# Balancer_4S.net
KiCad netlist of a schematic drawn in EAGLE
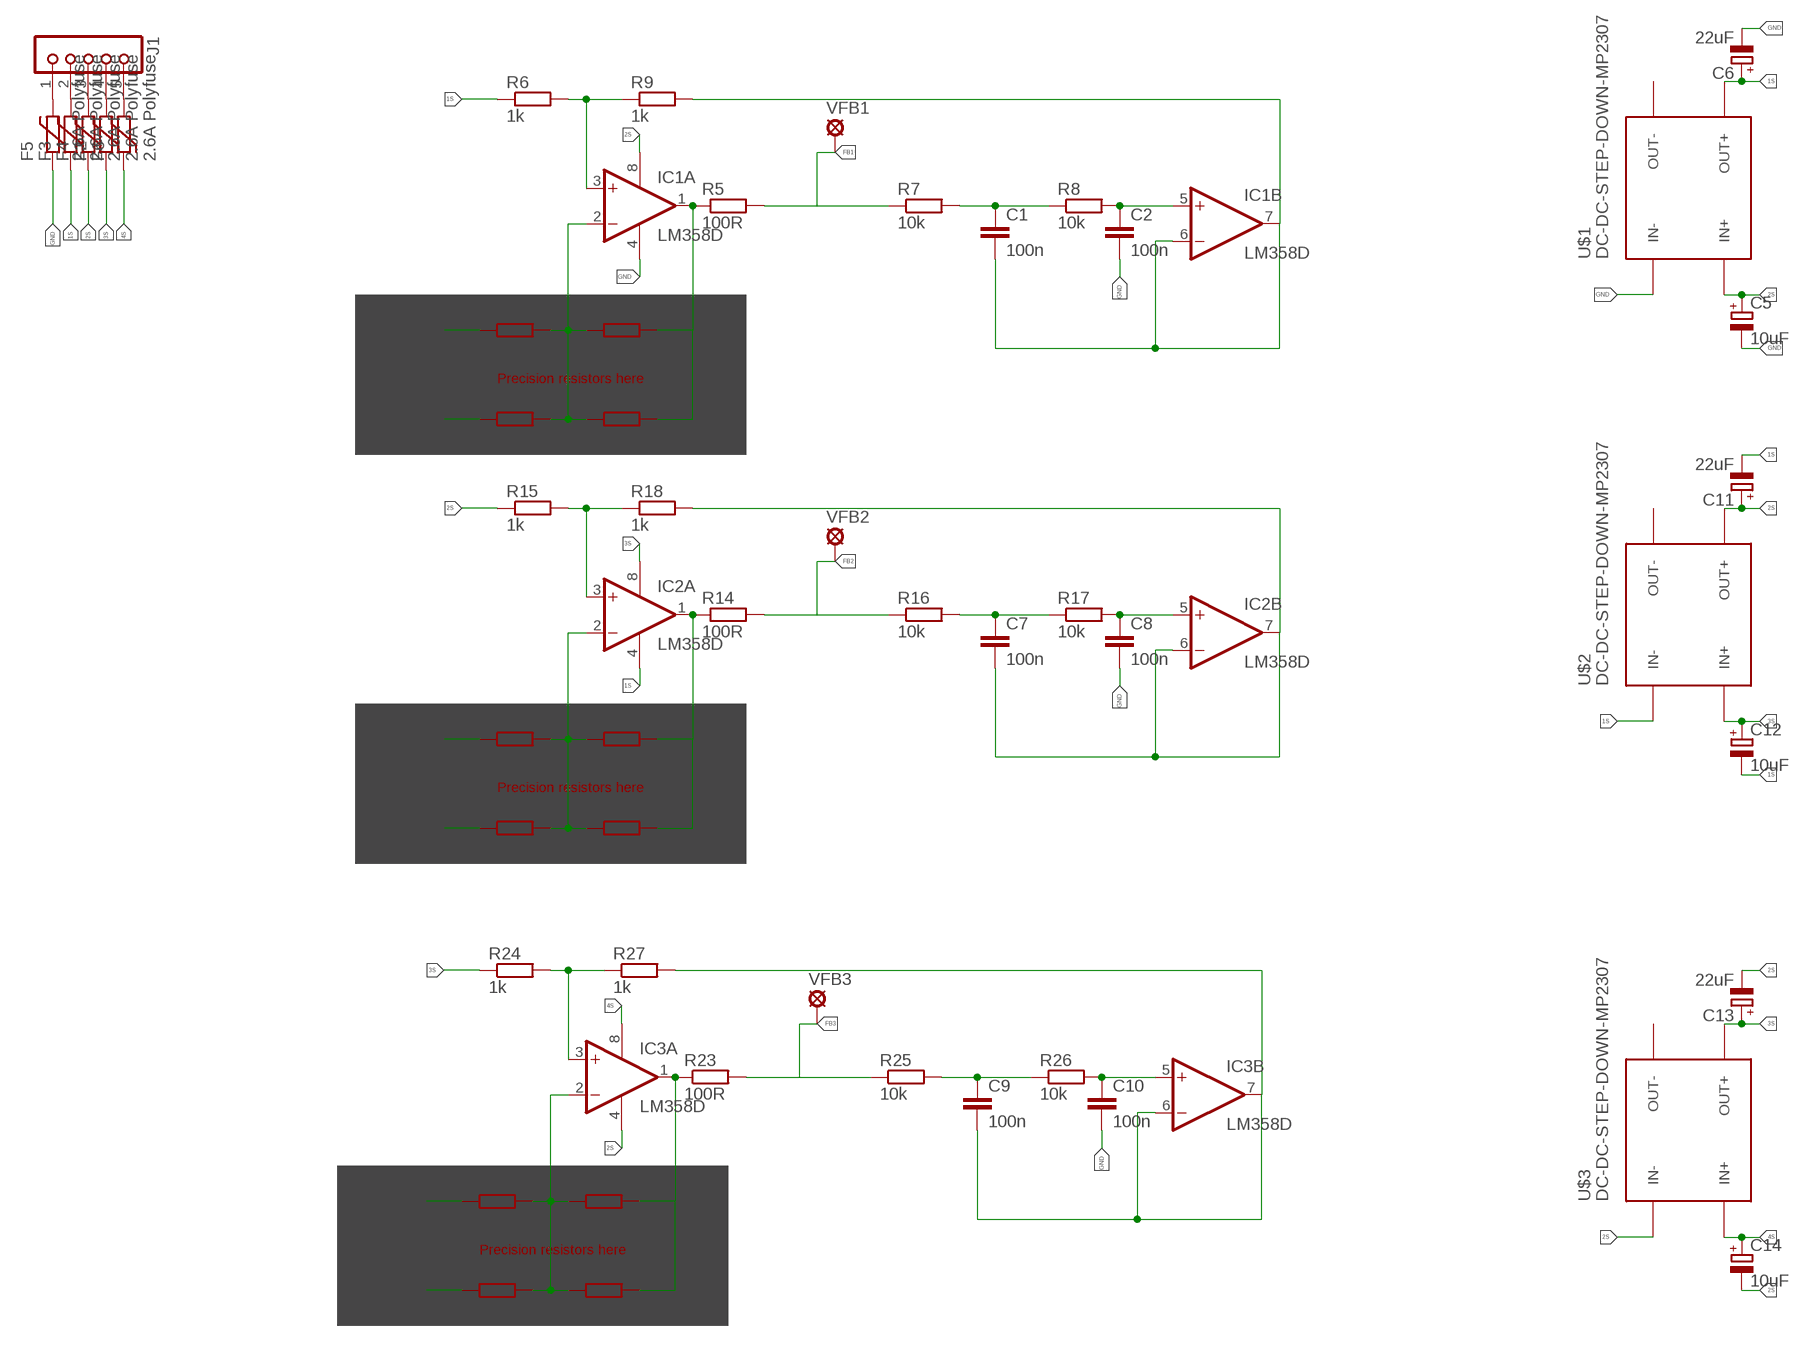
[diagram p0: schematic, sheet 1]

(export (version "E")
  (design (tool "Eeschema 10.0.6"))
  (components
    (comp (ref "C1")
      (value "100n")
      (footprint "eagle-import:C0805K")
      (libsource (lib "eagle-import") (part "C-EUC0805K"))
    )
    (comp (ref "C2")
      (value "100n")
      (footprint "eagle-import:C0805K")
      (libsource (lib "eagle-import") (part "C-EUC0805K"))
    )
    (comp (ref "C5")
      (value "10uF")
      (footprint "eagle-import:E2,5-6E")
      (libsource (lib "eagle-import") (part "CPOL-EUE2,5-6E"))
    )
    (comp (ref "C6")
      (value "22uF")
      (footprint "eagle-import:E2,5-6E")
      (libsource (lib "eagle-import") (part "CPOL-EUE2,5-6E"))
    )
    (comp (ref "C7")
      (value "100n")
      (footprint "eagle-import:C0805K")
      (libsource (lib "eagle-import") (part "C-EUC0805K"))
    )
    (comp (ref "C8")
      (value "100n")
      (footprint "eagle-import:C0805K")
      (libsource (lib "eagle-import") (part "C-EUC0805K"))
    )
    (comp (ref "C9")
      (value "100n")
      (footprint "eagle-import:C0805K")
      (libsource (lib "eagle-import") (part "C-EUC0805K"))
    )
    (comp (ref "C10")
      (value "100n")
      (footprint "eagle-import:C0805K")
      (libsource (lib "eagle-import") (part "C-EUC0805K"))
    )
    (comp (ref "C11")
      (value "22uF")
      (footprint "eagle-import:E2,5-6E")
      (libsource (lib "eagle-import") (part "CPOL-EUE2,5-6E"))
    )
    (comp (ref "C12")
      (value "10uF")
      (footprint "eagle-import:E2,5-6E")
      (libsource (lib "eagle-import") (part "CPOL-EUE2,5-6E"))
    )
    (comp (ref "C13")
      (value "22uF")
      (footprint "eagle-import:E2,5-6E")
      (libsource (lib "eagle-import") (part "CPOL-EUE2,5-6E"))
    )
    (comp (ref "C14")
      (value "10uF")
      (footprint "eagle-import:E2,5-6E")
      (libsource (lib "eagle-import") (part "CPOL-EUE2,5-6E"))
    )
    (comp (ref "F2")
      (value "2.6A Polyfuse")
      (footprint "eagle-import:1812L")
      (libsource (lib "eagle-import") (part "1812L"))
    )
    (comp (ref "F3")
      (value "2.6A Polyfuse")
      (footprint "eagle-import:1812L")
      (libsource (lib "eagle-import") (part "1812L"))
    )
    (comp (ref "F4")
      (value "2.6A Polyfuse")
      (footprint "eagle-import:1812L")
      (libsource (lib "eagle-import") (part "1812L"))
    )
    (comp (ref "F5")
      (value "2.6A Polyfuse")
      (footprint "eagle-import:1812L")
      (libsource (lib "eagle-import") (part "1812L"))
    )
    (comp (ref "F6")
      (value "2.6A Polyfuse")
      (footprint "eagle-import:1812L")
      (libsource (lib "eagle-import") (part "1812L"))
    )
    (comp (ref "IC1")
      (value "LM358D")
      (footprint "eagle-import:SO08")
      (libsource (lib "eagle-import") (part "LM358D"))
    )
    (comp (ref "IC2")
      (value "LM358D")
      (footprint "eagle-import:SO08")
      (libsource (lib "eagle-import") (part "LM358D"))
    )
    (comp (ref "IC3")
      (value "LM358D")
      (footprint "eagle-import:SO08")
      (libsource (lib "eagle-import") (part "LM358D"))
    )
    (comp (ref "J1")
      (value "JU05")
      (footprint "eagle-import:JU05")
      (libsource (lib "eagle-import") (part "JU05"))
    )
    (comp (ref "R1")
      (value "1k")
      (footprint "eagle-import:0204_7")
      (libsource (lib "eagle-import") (part "resistor_R-EU_0204/7"))
    )
    (comp (ref "R2")
      (value "1k")
      (footprint "eagle-import:0204_7")
      (libsource (lib "eagle-import") (part "resistor_R-EU_0204/7"))
    )
    (comp (ref "R3")
      (value "1k")
      (footprint "eagle-import:0204_7")
      (libsource (lib "eagle-import") (part "resistor_R-EU_0204/7"))
    )
    (comp (ref "R4")
      (value "1k")
      (footprint "eagle-import:0204_7")
      (libsource (lib "eagle-import") (part "resistor_R-EU_0204/7"))
    )
    (comp (ref "R5")
      (value "100R")
      (footprint "eagle-import:M0805")
      (libsource (lib "eagle-import") (part "R-EU_M0805"))
    )
    (comp (ref "R6")
      (value "1k")
      (footprint "eagle-import:M0805")
      (libsource (lib "eagle-import") (part "R-EU_M0805"))
    )
    (comp (ref "R7")
      (value "10k")
      (footprint "eagle-import:M0805")
      (libsource (lib "eagle-import") (part "R-EU_M0805"))
    )
    (comp (ref "R8")
      (value "10k")
      (footprint "eagle-import:M0805")
      (libsource (lib "eagle-import") (part "R-EU_M0805"))
    )
    (comp (ref "R9")
      (value "1k")
      (footprint "eagle-import:M0805")
      (libsource (lib "eagle-import") (part "R-EU_M0805"))
    )
    (comp (ref "R10")
      (value "1k")
      (footprint "eagle-import:0204_7")
      (libsource (lib "eagle-import") (part "resistor_R-EU_0204/7"))
    )
    (comp (ref "R11")
      (value "1k")
      (footprint "eagle-import:0204_7")
      (libsource (lib "eagle-import") (part "resistor_R-EU_0204/7"))
    )
    (comp (ref "R12")
      (value "1k")
      (footprint "eagle-import:0204_7")
      (libsource (lib "eagle-import") (part "resistor_R-EU_0204/7"))
    )
    (comp (ref "R13")
      (value "1k")
      (footprint "eagle-import:0204_7")
      (libsource (lib "eagle-import") (part "resistor_R-EU_0204/7"))
    )
    (comp (ref "R14")
      (value "100R")
      (footprint "eagle-import:M0805")
      (libsource (lib "eagle-import") (part "R-EU_M0805"))
    )
    (comp (ref "R15")
      (value "1k")
      (footprint "eagle-import:M0805")
      (libsource (lib "eagle-import") (part "R-EU_M0805"))
    )
    (comp (ref "R16")
      (value "10k")
      (footprint "eagle-import:M0805")
      (libsource (lib "eagle-import") (part "R-EU_M0805"))
    )
    (comp (ref "R17")
      (value "10k")
      (footprint "eagle-import:M0805")
      (libsource (lib "eagle-import") (part "R-EU_M0805"))
    )
    (comp (ref "R18")
      (value "1k")
      (footprint "eagle-import:M0805")
      (libsource (lib "eagle-import") (part "R-EU_M0805"))
    )
    (comp (ref "R19")
      (value "1k")
      (footprint "eagle-import:0204_7")
      (libsource (lib "eagle-import") (part "resistor_R-EU_0204/7"))
    )
    (comp (ref "R20")
      (value "1k")
      (footprint "eagle-import:0204_7")
      (libsource (lib "eagle-import") (part "resistor_R-EU_0204/7"))
    )
    (comp (ref "R21")
      (value "1k")
      (footprint "eagle-import:0204_7")
      (libsource (lib "eagle-import") (part "resistor_R-EU_0204/7"))
    )
    (comp (ref "R22")
      (value "1k")
      (footprint "eagle-import:0204_7")
      (libsource (lib "eagle-import") (part "resistor_R-EU_0204/7"))
    )
    (comp (ref "R23")
      (value "100R")
      (footprint "eagle-import:M0805")
      (libsource (lib "eagle-import") (part "R-EU_M0805"))
    )
    (comp (ref "R24")
      (value "1k")
      (footprint "eagle-import:M0805")
      (libsource (lib "eagle-import") (part "R-EU_M0805"))
    )
    (comp (ref "R25")
      (value "10k")
      (footprint "eagle-import:M0805")
      (libsource (lib "eagle-import") (part "R-EU_M0805"))
    )
    (comp (ref "R26")
      (value "10k")
      (footprint "eagle-import:M0805")
      (libsource (lib "eagle-import") (part "R-EU_M0805"))
    )
    (comp (ref "R27")
      (value "1k")
      (footprint "eagle-import:M0805")
      (libsource (lib "eagle-import") (part "R-EU_M0805"))
    )
    (comp (ref "U$1")
      (value "DC-DC-STEP-DOWN-MP2307")
      (footprint "eagle-import:DC-DC-STEP-DOWN-MP2307")
      (libsource (lib "eagle-import") (part "DC-DC-STEP-DOWN-MP2307"))
    )
    (comp (ref "U$2")
      (value "DC-DC-STEP-DOWN-MP2307")
      (footprint "eagle-import:DC-DC-STEP-DOWN-MP2307")
      (libsource (lib "eagle-import") (part "DC-DC-STEP-DOWN-MP2307"))
    )
    (comp (ref "U$3")
      (value "DC-DC-STEP-DOWN-MP2307")
      (footprint "eagle-import:DC-DC-STEP-DOWN-MP2307")
      (libsource (lib "eagle-import") (part "DC-DC-STEP-DOWN-MP2307"))
    )
    (comp (ref "VFB1")
      (value "MCS08")
      (footprint "eagle-import:MCS08")
      (libsource (lib "eagle-import") (part "MCS08"))
    )
    (comp (ref "VFB2")
      (value "MCS08")
      (footprint "eagle-import:MCS08")
      (libsource (lib "eagle-import") (part "MCS08"))
    )
    (comp (ref "VFB3")
      (value "MCS08")
      (footprint "eagle-import:MCS08")
      (libsource (lib "eagle-import") (part "MCS08"))
    )
  )
  (nets
    (net (code "1") (name "1S") (class "Default")
      (node (ref "C11") (pin "-") (pinfunction "-_-") (pintype "passive"))
      (node (ref "C12") (pin "-") (pinfunction "-_-") (pintype "passive"))
      (node (ref "C6") (pin "+") (pinfunction "+_+") (pintype "passive"))
      (node (ref "F3") (pin "P$1") (pinfunction "1_P$1") (pintype "passive"))
      (node (ref "IC2") (pin "4") (pinfunction "V-_4") (pintype "power_in"))
      (node (ref "R12") (pin "1") (pinfunction "1_1") (pintype "passive"))
      (node (ref "R6") (pin "1") (pinfunction "1_1") (pintype "passive"))
      (node (ref "U$1") (pin "OUT+") (pinfunction "OUT+_OUT+") (pintype "bidirectional"))
      (node (ref "U$2") (pin "IN-") (pinfunction "IN-_IN-") (pintype "bidirectional"))
    )
    (net (code "2") (name "2S") (class "Default")
      (node (ref "C11") (pin "+") (pinfunction "+_+") (pintype "passive"))
      (node (ref "C13") (pin "-") (pinfunction "-_-") (pintype "passive"))
      (node (ref "C14") (pin "-") (pinfunction "-_-") (pintype "passive"))
      (node (ref "C5") (pin "+") (pinfunction "+_+") (pintype "passive"))
      (node (ref "F4") (pin "P$1") (pinfunction "1_P$1") (pintype "passive"))
      (node (ref "IC1") (pin "8") (pinfunction "V+_8") (pintype "power_in"))
      (node (ref "IC3") (pin "4") (pinfunction "V-_4") (pintype "power_in"))
      (node (ref "R1") (pin "1") (pinfunction "1_1") (pintype "passive"))
      (node (ref "R15") (pin "1") (pinfunction "1_1") (pintype "passive"))
      (node (ref "R21") (pin "1") (pinfunction "1_1") (pintype "passive"))
      (node (ref "U$1") (pin "IN+") (pinfunction "IN+_IN+") (pintype "bidirectional"))
      (node (ref "U$2") (pin "OUT+") (pinfunction "OUT+_OUT+") (pintype "bidirectional"))
      (node (ref "U$3") (pin "IN-") (pinfunction "IN-_IN-") (pintype "bidirectional"))
    )
    (net (code "3") (name "3S") (class "Default")
      (node (ref "C12") (pin "+") (pinfunction "+_+") (pintype "passive"))
      (node (ref "C13") (pin "+") (pinfunction "+_+") (pintype "passive"))
      (node (ref "F2") (pin "P$1") (pinfunction "1_P$1") (pintype "passive"))
      (node (ref "IC2") (pin "8") (pinfunction "V+_8") (pintype "power_in"))
      (node (ref "R10") (pin "1") (pinfunction "1_1") (pintype "passive"))
      (node (ref "R24") (pin "1") (pinfunction "1_1") (pintype "passive"))
      (node (ref "U$2") (pin "IN+") (pinfunction "IN+_IN+") (pintype "bidirectional"))
      (node (ref "U$3") (pin "OUT+") (pinfunction "OUT+_OUT+") (pintype "bidirectional"))
    )
    (net (code "4") (name "4S") (class "Default")
      (node (ref "C14") (pin "+") (pinfunction "+_+") (pintype "passive"))
      (node (ref "F6") (pin "P$1") (pinfunction "1_P$1") (pintype "passive"))
      (node (ref "IC3") (pin "8") (pinfunction "V+_8") (pintype "power_in"))
      (node (ref "R19") (pin "1") (pinfunction "1_1") (pintype "passive"))
      (node (ref "U$3") (pin "IN+") (pinfunction "IN+_IN+") (pintype "bidirectional"))
    )
    (net (code "5") (name "FB1") (class "Default")
      (node (ref "R5") (pin "2") (pinfunction "2_2") (pintype "passive"))
      (node (ref "R7") (pin "1") (pinfunction "1_1") (pintype "passive"))
      (node (ref "VFB1") (pin "MP") (pinfunction "MP_MP") (pintype "passive"))
    )
    (net (code "6") (name "FB2") (class "Default")
      (node (ref "R14") (pin "2") (pinfunction "2_2") (pintype "passive"))
      (node (ref "R16") (pin "1") (pinfunction "1_1") (pintype "passive"))
      (node (ref "VFB2") (pin "MP") (pinfunction "MP_MP") (pintype "passive"))
    )
    (net (code "7") (name "FB3") (class "Default")
      (node (ref "R23") (pin "2") (pinfunction "2_2") (pintype "passive"))
      (node (ref "R25") (pin "1") (pinfunction "1_1") (pintype "passive"))
      (node (ref "VFB3") (pin "MP") (pinfunction "MP_MP") (pintype "passive"))
    )
    (net (code "8") (name "GND") (class "Default")
      (node (ref "C10") (pin "2") (pinfunction "2_2") (pintype "passive"))
      (node (ref "C2") (pin "2") (pinfunction "2_2") (pintype "passive"))
      (node (ref "C5") (pin "-") (pinfunction "-_-") (pintype "passive"))
      (node (ref "C6") (pin "-") (pinfunction "-_-") (pintype "passive"))
      (node (ref "C8") (pin "2") (pinfunction "2_2") (pintype "passive"))
      (node (ref "F5") (pin "P$1") (pinfunction "1_P$1") (pintype "passive"))
      (node (ref "IC1") (pin "4") (pinfunction "V-_4") (pintype "power_in"))
      (node (ref "R3") (pin "1") (pinfunction "1_1") (pintype "passive"))
      (node (ref "U$1") (pin "IN-") (pinfunction "IN-_IN-") (pintype "bidirectional"))
    )
    (net (code "9") (name "Net-(C1-Pad1)") (class "Default")
      (node (ref "C1") (pin "1") (pinfunction "1_1") (pintype "passive"))
      (node (ref "R7") (pin "2") (pinfunction "2_2") (pintype "passive"))
      (node (ref "R8") (pin "1") (pinfunction "1_1") (pintype "passive"))
    )
    (net (code "10") (name "Net-(C7-Pad1)") (class "Default")
      (node (ref "C7") (pin "1") (pinfunction "1_1") (pintype "passive"))
      (node (ref "R16") (pin "2") (pinfunction "2_2") (pintype "passive"))
      (node (ref "R17") (pin "1") (pinfunction "1_1") (pintype "passive"))
    )
    (net (code "11") (name "Net-(C9-Pad1)") (class "Default")
      (node (ref "C9") (pin "1") (pinfunction "1_1") (pintype "passive"))
      (node (ref "R25") (pin "2") (pinfunction "2_2") (pintype "passive"))
      (node (ref "R26") (pin "1") (pinfunction "1_1") (pintype "passive"))
    )
    (net (code "12") (name "Net-(F2-2)") (class "Default")
      (node (ref "F2") (pin "P$2") (pinfunction "2_P$2") (pintype "passive"))
      (node (ref "J1") (pin "4") (pinfunction "4_4") (pintype "passive"))
    )
    (net (code "13") (name "Net-(F3-2)") (class "Default")
      (node (ref "F3") (pin "P$2") (pinfunction "2_P$2") (pintype "passive"))
      (node (ref "J1") (pin "2") (pinfunction "2_2") (pintype "passive"))
    )
    (net (code "14") (name "Net-(F4-2)") (class "Default")
      (node (ref "F4") (pin "P$2") (pinfunction "2_P$2") (pintype "passive"))
      (node (ref "J1") (pin "3") (pinfunction "3_3") (pintype "passive"))
    )
    (net (code "15") (name "Net-(F5-2)") (class "Default")
      (node (ref "F5") (pin "P$2") (pinfunction "2_P$2") (pintype "passive"))
      (node (ref "J1") (pin "1") (pinfunction "1_1") (pintype "passive"))
    )
    (net (code "16") (name "Net-(F6-2)") (class "Default")
      (node (ref "F6") (pin "P$2") (pinfunction "2_P$2") (pintype "passive"))
      (node (ref "J1") (pin "5") (pinfunction "5_5") (pintype "passive"))
    )
    (net (code "17") (name "Net-(IC1A-+IN)") (class "Default")
      (node (ref "IC1") (pin "3") (pinfunction "+IN_3") (pintype "input"))
      (node (ref "R6") (pin "2") (pinfunction "2_2") (pintype "passive"))
      (node (ref "R9") (pin "1") (pinfunction "1_1") (pintype "passive"))
    )
    (net (code "18") (name "Net-(IC1A--IN)") (class "Default")
      (node (ref "IC1") (pin "2") (pinfunction "-IN_2") (pintype "input"))
      (node (ref "R1") (pin "2") (pinfunction "2_2") (pintype "passive"))
      (node (ref "R2") (pin "1") (pinfunction "1_1") (pintype "passive"))
      (node (ref "R3") (pin "2") (pinfunction "2_2") (pintype "passive"))
      (node (ref "R4") (pin "1") (pinfunction "1_1") (pintype "passive"))
    )
    (net (code "19") (name "Net-(IC1A-OUT)") (class "Default")
      (node (ref "IC1") (pin "1") (pinfunction "OUT_1") (pintype "output"))
      (node (ref "R2") (pin "2") (pinfunction "2_2") (pintype "passive"))
      (node (ref "R4") (pin "2") (pinfunction "2_2") (pintype "passive"))
      (node (ref "R5") (pin "1") (pinfunction "1_1") (pintype "passive"))
    )
    (net (code "20") (name "Net-(IC1B-+IN)") (class "Default")
      (node (ref "C2") (pin "1") (pinfunction "1_1") (pintype "passive"))
      (node (ref "IC1") (pin "5") (pinfunction "+IN_5") (pintype "input"))
      (node (ref "R8") (pin "2") (pinfunction "2_2") (pintype "passive"))
    )
    (net (code "21") (name "Net-(IC1B--IN)") (class "Default")
      (node (ref "C1") (pin "2") (pinfunction "2_2") (pintype "passive"))
      (node (ref "IC1") (pin "6") (pinfunction "-IN_6") (pintype "input"))
      (node (ref "IC1") (pin "7") (pinfunction "OUT_7") (pintype "output"))
      (node (ref "R9") (pin "2") (pinfunction "2_2") (pintype "passive"))
    )
    (net (code "22") (name "Net-(IC2A-+IN)") (class "Default")
      (node (ref "IC2") (pin "3") (pinfunction "+IN_3") (pintype "input"))
      (node (ref "R15") (pin "2") (pinfunction "2_2") (pintype "passive"))
      (node (ref "R18") (pin "1") (pinfunction "1_1") (pintype "passive"))
    )
    (net (code "23") (name "Net-(IC2A--IN)") (class "Default")
      (node (ref "IC2") (pin "2") (pinfunction "-IN_2") (pintype "input"))
      (node (ref "R10") (pin "2") (pinfunction "2_2") (pintype "passive"))
      (node (ref "R11") (pin "1") (pinfunction "1_1") (pintype "passive"))
      (node (ref "R12") (pin "2") (pinfunction "2_2") (pintype "passive"))
      (node (ref "R13") (pin "1") (pinfunction "1_1") (pintype "passive"))
    )
    (net (code "24") (name "Net-(IC2A-OUT)") (class "Default")
      (node (ref "IC2") (pin "1") (pinfunction "OUT_1") (pintype "output"))
      (node (ref "R11") (pin "2") (pinfunction "2_2") (pintype "passive"))
      (node (ref "R13") (pin "2") (pinfunction "2_2") (pintype "passive"))
      (node (ref "R14") (pin "1") (pinfunction "1_1") (pintype "passive"))
    )
    (net (code "25") (name "Net-(IC2B-+IN)") (class "Default")
      (node (ref "C8") (pin "1") (pinfunction "1_1") (pintype "passive"))
      (node (ref "IC2") (pin "5") (pinfunction "+IN_5") (pintype "input"))
      (node (ref "R17") (pin "2") (pinfunction "2_2") (pintype "passive"))
    )
    (net (code "26") (name "Net-(IC2B--IN)") (class "Default")
      (node (ref "C7") (pin "2") (pinfunction "2_2") (pintype "passive"))
      (node (ref "IC2") (pin "6") (pinfunction "-IN_6") (pintype "input"))
      (node (ref "IC2") (pin "7") (pinfunction "OUT_7") (pintype "output"))
      (node (ref "R18") (pin "2") (pinfunction "2_2") (pintype "passive"))
    )
    (net (code "27") (name "Net-(IC3A-+IN)") (class "Default")
      (node (ref "IC3") (pin "3") (pinfunction "+IN_3") (pintype "input"))
      (node (ref "R24") (pin "2") (pinfunction "2_2") (pintype "passive"))
      (node (ref "R27") (pin "1") (pinfunction "1_1") (pintype "passive"))
    )
    (net (code "28") (name "Net-(IC3A--IN)") (class "Default")
      (node (ref "IC3") (pin "2") (pinfunction "-IN_2") (pintype "input"))
      (node (ref "R19") (pin "2") (pinfunction "2_2") (pintype "passive"))
      (node (ref "R20") (pin "1") (pinfunction "1_1") (pintype "passive"))
      (node (ref "R21") (pin "2") (pinfunction "2_2") (pintype "passive"))
      (node (ref "R22") (pin "1") (pinfunction "1_1") (pintype "passive"))
    )
    (net (code "29") (name "Net-(IC3A-OUT)") (class "Default")
      (node (ref "IC3") (pin "1") (pinfunction "OUT_1") (pintype "output"))
      (node (ref "R20") (pin "2") (pinfunction "2_2") (pintype "passive"))
      (node (ref "R22") (pin "2") (pinfunction "2_2") (pintype "passive"))
      (node (ref "R23") (pin "1") (pinfunction "1_1") (pintype "passive"))
    )
    (net (code "30") (name "Net-(IC3B-+IN)") (class "Default")
      (node (ref "C10") (pin "1") (pinfunction "1_1") (pintype "passive"))
      (node (ref "IC3") (pin "5") (pinfunction "+IN_5") (pintype "input"))
      (node (ref "R26") (pin "2") (pinfunction "2_2") (pintype "passive"))
    )
    (net (code "31") (name "Net-(IC3B--IN)") (class "Default")
      (node (ref "C9") (pin "2") (pinfunction "2_2") (pintype "passive"))
      (node (ref "IC3") (pin "6") (pinfunction "-IN_6") (pintype "input"))
      (node (ref "IC3") (pin "7") (pinfunction "OUT_7") (pintype "output"))
      (node (ref "R27") (pin "2") (pinfunction "2_2") (pintype "passive"))
    )
    (net (code "32") (name "unconnected-(U$1-PadOUT-)") (class "Default")
      (node (ref "U$1") (pin "OUT-") (pinfunction "OUT-_OUT-") (pintype "bidirectional"))
    )
    (net (code "33") (name "unconnected-(U$2-PadOUT-)") (class "Default")
      (node (ref "U$2") (pin "OUT-") (pinfunction "OUT-_OUT-") (pintype "bidirectional"))
    )
    (net (code "34") (name "unconnected-(U$3-PadOUT-)") (class "Default")
      (node (ref "U$3") (pin "OUT-") (pinfunction "OUT-_OUT-") (pintype "bidirectional"))
    )
  )
)
